# mcu.net
KiCad netlist of a schematic drawn in Altium Designer
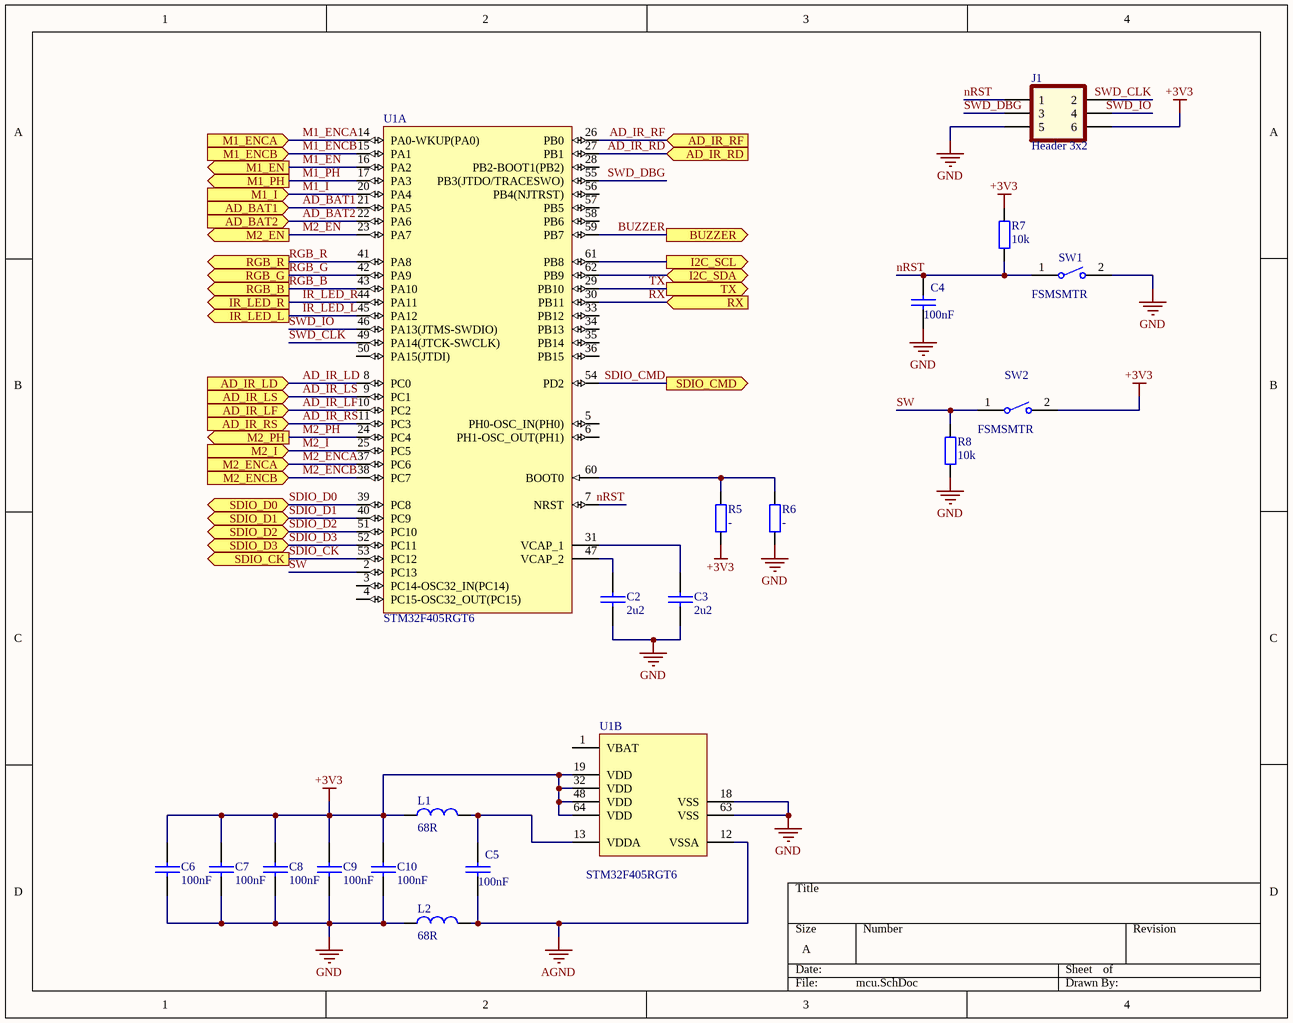
[diagram p0: mcu.SchDoc]

(export (version "E")
  (design (tool "Eeschema 10.0.6"))
  (components
    (comp (ref "C2")
      (value "2u2")
      (footprint "C0402-Paste")
      (description "CAP CER 0.1UF 16V Y5V 0402")
      (fields (field (name "MANUFACTURER") "Samsung Electro-Mechanics"))
      (libsource (lib "Passives") (part "C-0402"))
    )
    (comp (ref "C3")
      (value "2u2")
      (footprint "C0402-Paste")
      (description "CAP CER 0.1UF 16V Y5V 0402")
      (fields (field (name "MANUFACTURER") "Samsung Electro-Mechanics"))
      (libsource (lib "Passives") (part "C-0402"))
    )
    (comp (ref "C4")
      (value "100nF")
      (footprint "C0402-Paste")
      (description "CAP CER 0.1UF 16V Y5V 0402")
      (fields (field (name "MANUFACTURER") "Samsung Electro-Mechanics"))
      (libsource (lib "Passives") (part "C-0402"))
    )
    (comp (ref "C5")
      (value "100nF")
      (footprint "C0402-Paste")
      (description "CAP CER 0.1UF 16V Y5V 0402")
      (fields (field (name "MANUFACTURER") "Samsung Electro-Mechanics"))
      (libsource (lib "Passives") (part "C-0402"))
    )
    (comp (ref "C6")
      (value "100nF")
      (footprint "C0402-Paste")
      (description "CAP CER 0.1UF 16V Y5V 0402")
      (fields (field (name "MANUFACTURER") "Samsung Electro-Mechanics"))
      (libsource (lib "Passives") (part "C-0402"))
    )
    (comp (ref "C7")
      (value "100nF")
      (footprint "C0402-Paste")
      (description "CAP CER 0.1UF 16V Y5V 0402")
      (fields (field (name "MANUFACTURER") "Samsung Electro-Mechanics"))
      (libsource (lib "Passives") (part "C-0402"))
    )
    (comp (ref "C8")
      (value "100nF")
      (footprint "C0402-Paste")
      (description "CAP CER 0.1UF 16V Y5V 0402")
      (fields (field (name "MANUFACTURER") "Samsung Electro-Mechanics"))
      (libsource (lib "Passives") (part "C-0402"))
    )
    (comp (ref "C9")
      (value "100nF")
      (footprint "C0402-Paste")
      (description "CAP CER 0.1UF 16V Y5V 0402")
      (fields (field (name "MANUFACTURER") "Samsung Electro-Mechanics"))
      (libsource (lib "Passives") (part "C-0402"))
    )
    (comp (ref "C10")
      (value "100nF")
      (footprint "C0402-Paste")
      (description "CAP CER 0.1UF 16V Y5V 0402")
      (fields (field (name "MANUFACTURER") "Samsung Electro-Mechanics"))
      (libsource (lib "Passives") (part "C-0402"))
    )
    (comp (ref "J1")
      (value "Header 3x2")
      (footprint "CON-6x2")
      (description "CONN HEADER VERT 6POS 2.54MM")
      (fields (field (name "MANUFACTURER") "Sullins Connector Solutions"))
      (libsource (lib "Connectors") (part "Header 3x2"))
    )
    (comp (ref "L1")
      (value "68R")
      (footprint "L0603_PASTE")
      (description "FERRITE BEAD 0603")
      (fields (field (name "MANUFACTURER") "Laird-Signal Integrity Products"))
      (libsource (lib "Passives") (part "L-0603"))
    )
    (comp (ref "L2")
      (value "68R")
      (footprint "L0603_PASTE")
      (description "FERRITE BEAD 0603")
      (fields (field (name "MANUFACTURER") "Laird-Signal Integrity Products"))
      (libsource (lib "Passives") (part "L-0603"))
    )
    (comp (ref "R5")
      (value "-")
      (footprint "R0402-Paste")
      (description "RES SMD 0402")
      (libsource (lib "Passives") (part "R-0402"))
    )
    (comp (ref "R6")
      (value "-")
      (footprint "R0402-Paste")
      (description "RES SMD 0402")
      (libsource (lib "Passives") (part "R-0402"))
    )
    (comp (ref "R7")
      (value "10k")
      (footprint "R0603_PASTE")
      (description "RES SMD 0603")
      (libsource (lib "Passives") (part "R-0603"))
    )
    (comp (ref "R8")
      (value "10k")
      (footprint "R0603_PASTE")
      (description "RES SMD 0603")
      (libsource (lib "Passives") (part "R-0603"))
    )
    (comp (ref "SW1")
      (value "FSMSMTR")
      (footprint "TECO-FSMSMTR_V")
      (description "FSMSM Push Button Switch, 50 mA, -35 to 85 degC, 2-Pin SMD, RoHS, Tape and Reel")
      (fields (field (name "MANUFACTURER") "TE Connectivity"))
      (libsource (lib "Altium Content Vault") (part "SW-SPST-2_C"))
    )
    (comp (ref "SW2")
      (value "FSMSMTR")
      (footprint "TECO-FSMSMTR_V")
      (description "FSMSM Push Button Switch, 50 mA, -35 to 85 degC, 2-Pin SMD, RoHS, Tape and Reel")
      (fields (field (name "MANUFACTURER") "TE Connectivity"))
      (libsource (lib "Altium Content Vault") (part "SW-SPST-2_C"))
    )
    (comp (ref "U1")
      (value "STM32F405RGT6")
      (footprint "STM-LQFP64_M")
      (fields (field (name "MANUFACTURER") "STMicroelectronics"))
      (libsource (lib "Altium Content Vault") (part "MC-ARM-STM32F4X5-SQ64"))
    )
  )
  (nets
    (net (code "1") (name "+3V3") (class "Default")
      (node (ref "C10") (pin "2") (pintype "passive"))
      (node (ref "C6") (pin "2") (pintype "passive"))
      (node (ref "C7") (pin "2") (pintype "passive"))
      (node (ref "C8") (pin "2") (pintype "passive"))
      (node (ref "C9") (pin "2") (pintype "passive"))
      (node (ref "J1") (pin "6") (pinfunction "6_6") (pintype "passive"))
      (node (ref "L1") (pin "1") (pinfunction "1_1") (pintype "passive"))
      (node (ref "R5") (pin "2") (pinfunction "2_2") (pintype "passive"))
      (node (ref "R7") (pin "1") (pinfunction "1_1") (pintype "passive"))
      (node (ref "SW2") (pin "2") (pinfunction "2_2") (pintype "passive"))
      (node (ref "U1") (pin "19") (pinfunction "VDD_19") (pintype "power_in"))
      (node (ref "U1") (pin "32") (pinfunction "VDD_32") (pintype "power_in"))
      (node (ref "U1") (pin "48") (pinfunction "VDD_48") (pintype "power_in"))
      (node (ref "U1") (pin "64") (pinfunction "VDD_64") (pintype "power_in"))
    )
    (net (code "2") (name "/AD_BAT1") (class "Default")
      (node (ref "U1") (pin "21") (pinfunction "PA5_21") (pintype "bidirectional"))
    )
    (net (code "3") (name "/AD_BAT2") (class "Default")
      (node (ref "U1") (pin "22") (pinfunction "PA6_22") (pintype "bidirectional"))
    )
    (net (code "4") (name "/AD_IR_LD") (class "Default")
      (node (ref "U1") (pin "8") (pinfunction "PC0_8") (pintype "bidirectional"))
    )
    (net (code "5") (name "/AD_IR_LF") (class "Default")
      (node (ref "U1") (pin "10") (pinfunction "PC2_10") (pintype "bidirectional"))
    )
    (net (code "6") (name "/AD_IR_LS") (class "Default")
      (node (ref "U1") (pin "9") (pinfunction "PC1_9") (pintype "bidirectional"))
    )
    (net (code "7") (name "/AD_IR_RD") (class "Default")
      (node (ref "U1") (pin "27") (pinfunction "PB1_27") (pintype "bidirectional"))
    )
    (net (code "8") (name "/AD_IR_RF") (class "Default")
      (node (ref "U1") (pin "26") (pinfunction "PB0_26") (pintype "bidirectional"))
    )
    (net (code "9") (name "/AD_IR_RS") (class "Default")
      (node (ref "U1") (pin "11") (pinfunction "PC3_11") (pintype "bidirectional"))
    )
    (net (code "10") (name "/BUZZER") (class "Default")
      (node (ref "U1") (pin "59") (pinfunction "PB7_59") (pintype "bidirectional"))
    )
    (net (code "11") (name "/I2C_SCL") (class "Default")
      (node (ref "U1") (pin "61") (pinfunction "PB8_61") (pintype "bidirectional"))
    )
    (net (code "12") (name "/I2C_SDA") (class "Default")
      (node (ref "U1") (pin "62") (pinfunction "PB9_62") (pintype "bidirectional"))
    )
    (net (code "13") (name "/IR_LED_L") (class "Default")
      (node (ref "U1") (pin "45") (pinfunction "PA12_45") (pintype "bidirectional"))
    )
    (net (code "14") (name "/IR_LED_R") (class "Default")
      (node (ref "U1") (pin "44") (pinfunction "PA11_44") (pintype "bidirectional"))
    )
    (net (code "15") (name "/M1_EN") (class "Default")
      (node (ref "U1") (pin "16") (pinfunction "PA2_16") (pintype "bidirectional"))
    )
    (net (code "16") (name "/M1_ENCA") (class "Default")
      (node (ref "U1") (pin "14") (pinfunction "PA0-WKUP(PA0)_14") (pintype "bidirectional"))
    )
    (net (code "17") (name "/M1_ENCB") (class "Default")
      (node (ref "U1") (pin "15") (pinfunction "PA1_15") (pintype "bidirectional"))
    )
    (net (code "18") (name "/M1_I") (class "Default")
      (node (ref "U1") (pin "20") (pinfunction "PA4_20") (pintype "bidirectional"))
    )
    (net (code "19") (name "/M1_PH") (class "Default")
      (node (ref "U1") (pin "17") (pinfunction "PA3_17") (pintype "bidirectional"))
    )
    (net (code "20") (name "/M2_EN") (class "Default")
      (node (ref "U1") (pin "23") (pinfunction "PA7_23") (pintype "bidirectional"))
    )
    (net (code "21") (name "/M2_ENCA") (class "Default")
      (node (ref "U1") (pin "37") (pinfunction "PC6_37") (pintype "bidirectional"))
    )
    (net (code "22") (name "/M2_ENCB") (class "Default")
      (node (ref "U1") (pin "38") (pinfunction "PC7_38") (pintype "bidirectional"))
    )
    (net (code "23") (name "/M2_I") (class "Default")
      (node (ref "U1") (pin "25") (pinfunction "PC5_25") (pintype "bidirectional"))
    )
    (net (code "24") (name "/M2_PH") (class "Default")
      (node (ref "U1") (pin "24") (pinfunction "PC4_24") (pintype "bidirectional"))
    )
    (net (code "25") (name "/RGB_B") (class "Default")
      (node (ref "U1") (pin "43") (pinfunction "PA10_43") (pintype "bidirectional"))
    )
    (net (code "26") (name "/RGB_G") (class "Default")
      (node (ref "U1") (pin "42") (pinfunction "PA9_42") (pintype "bidirectional"))
    )
    (net (code "27") (name "/RGB_R") (class "Default")
      (node (ref "U1") (pin "41") (pinfunction "PA8_41") (pintype "bidirectional"))
    )
    (net (code "28") (name "/RX") (class "Default")
      (node (ref "U1") (pin "30") (pinfunction "PB11_30") (pintype "bidirectional"))
    )
    (net (code "29") (name "/SDIO_CK") (class "Default")
      (node (ref "U1") (pin "53") (pinfunction "PC12_53") (pintype "bidirectional"))
    )
    (net (code "30") (name "/SDIO_CMD") (class "Default")
      (node (ref "U1") (pin "54") (pinfunction "PD2_54") (pintype "bidirectional"))
    )
    (net (code "31") (name "/SDIO_D0") (class "Default")
      (node (ref "U1") (pin "39") (pinfunction "PC8_39") (pintype "bidirectional"))
    )
    (net (code "32") (name "/SDIO_D1") (class "Default")
      (node (ref "U1") (pin "40") (pinfunction "PC9_40") (pintype "bidirectional"))
    )
    (net (code "33") (name "/SDIO_D2") (class "Default")
      (node (ref "U1") (pin "51") (pinfunction "PC10_51") (pintype "bidirectional"))
    )
    (net (code "34") (name "/SDIO_D3") (class "Default")
      (node (ref "U1") (pin "52") (pinfunction "PC11_52") (pintype "bidirectional"))
    )
    (net (code "35") (name "/SW") (class "Default")
      (node (ref "R8") (pin "1") (pinfunction "1_1") (pintype "passive"))
      (node (ref "SW2") (pin "1") (pinfunction "1_1") (pintype "passive"))
      (node (ref "U1") (pin "2") (pinfunction "PC13_2") (pintype "bidirectional"))
    )
    (net (code "36") (name "/SWD_CLK") (class "Default")
      (node (ref "J1") (pin "2") (pinfunction "2_2") (pintype "passive"))
      (node (ref "U1") (pin "49") (pinfunction "PA14(JTCK-SWCLK)_49") (pintype "bidirectional"))
    )
    (net (code "37") (name "/SWD_DBG") (class "Default")
      (node (ref "J1") (pin "3") (pinfunction "3_3") (pintype "passive"))
      (node (ref "U1") (pin "55") (pinfunction "PB3(JTDO/TRACESWO)_55") (pintype "bidirectional"))
    )
    (net (code "38") (name "/SWD_IO") (class "Default")
      (node (ref "J1") (pin "4") (pinfunction "4_4") (pintype "passive"))
      (node (ref "U1") (pin "46") (pinfunction "PA13(JTMS-SWDIO)_46") (pintype "bidirectional"))
    )
    (net (code "39") (name "/TX") (class "Default")
      (node (ref "U1") (pin "29") (pinfunction "PB10_29") (pintype "bidirectional"))
    )
    (net (code "40") (name "/nRST") (class "Default")
      (node (ref "C4") (pin "2") (pintype "passive"))
      (node (ref "J1") (pin "1") (pinfunction "1_1") (pintype "passive"))
      (node (ref "R7") (pin "2") (pinfunction "2_2") (pintype "passive"))
      (node (ref "SW1") (pin "1") (pinfunction "1_1") (pintype "passive"))
      (node (ref "U1") (pin "7") (pinfunction "NRST_7") (pintype "bidirectional"))
    )
    (net (code "41") (name "AGND") (class "Default")
      (node (ref "C5") (pin "1") (pintype "passive"))
      (node (ref "L2") (pin "2") (pinfunction "2_2") (pintype "passive"))
      (node (ref "U1") (pin "12") (pinfunction "VSSA_12") (pintype "power_in"))
    )
    (net (code "42") (name "GND") (class "Default")
      (node (ref "C10") (pin "1") (pintype "passive"))
      (node (ref "C2") (pin "1") (pintype "passive"))
      (node (ref "C3") (pin "1") (pintype "passive"))
      (node (ref "C4") (pin "1") (pintype "passive"))
      (node (ref "C6") (pin "1") (pintype "passive"))
      (node (ref "C7") (pin "1") (pintype "passive"))
      (node (ref "C8") (pin "1") (pintype "passive"))
      (node (ref "C9") (pin "1") (pintype "passive"))
      (node (ref "J1") (pin "5") (pinfunction "5_5") (pintype "passive"))
      (node (ref "L2") (pin "1") (pinfunction "1_1") (pintype "passive"))
      (node (ref "R6") (pin "2") (pinfunction "2_2") (pintype "passive"))
      (node (ref "R8") (pin "2") (pinfunction "2_2") (pintype "passive"))
      (node (ref "SW1") (pin "2") (pinfunction "2_2") (pintype "passive"))
      (node (ref "U1") (pin "18") (pinfunction "VSS_18") (pintype "power_in"))
      (node (ref "U1") (pin "63") (pinfunction "VSS_63") (pintype "power_in"))
    )
    (net (code "43") (name "Net-(U1A-BOOT0)") (class "Default")
      (node (ref "R5") (pin "1") (pinfunction "1_1") (pintype "passive"))
      (node (ref "R6") (pin "1") (pinfunction "1_1") (pintype "passive"))
      (node (ref "U1") (pin "60") (pinfunction "BOOT0_60") (pintype "input"))
    )
    (net (code "44") (name "Net-(U1A-VCAP_1)") (class "Default")
      (node (ref "C3") (pin "2") (pintype "passive"))
      (node (ref "U1") (pin "31") (pinfunction "VCAP_1_31") (pintype "power_in"))
    )
    (net (code "45") (name "Net-(U1A-VCAP_2)") (class "Default")
      (node (ref "C2") (pin "2") (pintype "passive"))
      (node (ref "U1") (pin "47") (pinfunction "VCAP_2_47") (pintype "power_in"))
    )
    (net (code "46") (name "Net-(U1B-VDDA)") (class "Default")
      (node (ref "C5") (pin "2") (pintype "passive"))
      (node (ref "L1") (pin "2") (pinfunction "2_2") (pintype "passive"))
      (node (ref "U1") (pin "13") (pinfunction "VDDA_13") (pintype "power_in"))
    )
    (net (code "47") (name "unconnected-(U1A-PA15(JTDI)-Pad50)") (class "Default")
      (node (ref "U1") (pin "50") (pinfunction "PA15(JTDI)_50") (pintype "bidirectional"))
    )
    (net (code "48") (name "unconnected-(U1A-PB2-BOOT1(PB2)-Pad28)") (class "Default")
      (node (ref "U1") (pin "28") (pinfunction "PB2-BOOT1(PB2)_28") (pintype "bidirectional"))
    )
    (net (code "49") (name "unconnected-(U1A-PB4(NJTRST)-Pad56)") (class "Default")
      (node (ref "U1") (pin "56") (pinfunction "PB4(NJTRST)_56") (pintype "bidirectional"))
    )
    (net (code "50") (name "unconnected-(U1A-PB5-Pad57)") (class "Default")
      (node (ref "U1") (pin "57") (pinfunction "PB5_57") (pintype "bidirectional"))
    )
    (net (code "51") (name "unconnected-(U1A-PB6-Pad58)") (class "Default")
      (node (ref "U1") (pin "58") (pinfunction "PB6_58") (pintype "bidirectional"))
    )
    (net (code "52") (name "unconnected-(U1A-PB12-Pad33)") (class "Default")
      (node (ref "U1") (pin "33") (pinfunction "PB12_33") (pintype "bidirectional"))
    )
    (net (code "53") (name "unconnected-(U1A-PB13-Pad34)") (class "Default")
      (node (ref "U1") (pin "34") (pinfunction "PB13_34") (pintype "bidirectional"))
    )
    (net (code "54") (name "unconnected-(U1A-PB14-Pad35)") (class "Default")
      (node (ref "U1") (pin "35") (pinfunction "PB14_35") (pintype "bidirectional"))
    )
    (net (code "55") (name "unconnected-(U1A-PB15-Pad36)") (class "Default")
      (node (ref "U1") (pin "36") (pinfunction "PB15_36") (pintype "bidirectional"))
    )
    (net (code "56") (name "unconnected-(U1A-PC14-OSC32_IN(PC14)-Pad3)") (class "Default")
      (node (ref "U1") (pin "3") (pinfunction "PC14-OSC32_IN(PC14)_3") (pintype "bidirectional"))
    )
    (net (code "57") (name "unconnected-(U1A-PC15-OSC32_OUT(PC15)-Pad4)") (class "Default")
      (node (ref "U1") (pin "4") (pinfunction "PC15-OSC32_OUT(PC15)_4") (pintype "bidirectional"))
    )
    (net (code "58") (name "unconnected-(U1A-PH0-OSC_IN(PH0)-Pad5)") (class "Default")
      (node (ref "U1") (pin "5") (pinfunction "PH0-OSC_IN(PH0)_5") (pintype "bidirectional"))
    )
    (net (code "59") (name "unconnected-(U1A-PH1-OSC_OUT(PH1)-Pad6)") (class "Default")
      (node (ref "U1") (pin "6") (pinfunction "PH1-OSC_OUT(PH1)_6") (pintype "bidirectional"))
    )
    (net (code "60") (name "unconnected-(U1B-VBAT-Pad1)") (class "Default")
      (node (ref "U1") (pin "1") (pinfunction "VBAT_1") (pintype "power_in"))
    )
  )
)
